# 5_power_supply.net
KiCad netlist of a schematic drawn in Altium Designer
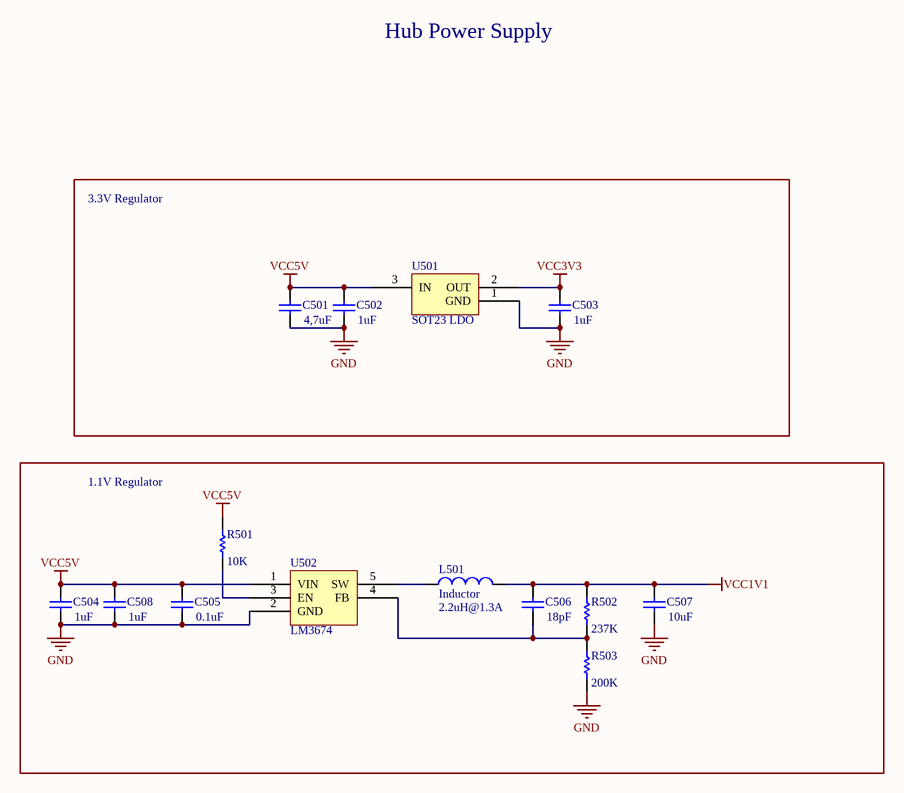
[diagram p0: 5_power_supply.SchDoc]

(export (version "E")
  (design (tool "Eeschema 10.0.6"))
  (components
    (comp (ref "C501")
      (value "4,7uF")
      (footprint "C0603[1608]")
      (description "Capacitor")
      (fields (field (name "LCSC PART #") "C19666") (field (name "MRF.PART") "CL10A475KO8NNNC"))
      (libsource (lib "Miscellaneous Devices") (part "Cap"))
    )
    (comp (ref "C502")
      (value "1uF")
      (footprint "C0603[1608]")
      (description "Capacitor")
      (fields (field (name "MFG") "KEMET") (field (name "LCSC PART #") "C15849"))
      (libsource (lib "Miscellaneous Devices") (part "Cap"))
    )
    (comp (ref "C503")
      (value "1uF")
      (footprint "C0603[1608]")
      (description "Capacitor")
      (fields (field (name "MFG") "KEMET") (field (name "LCSC PART #") "C15849"))
      (libsource (lib "Miscellaneous Devices") (part "Cap"))
    )
    (comp (ref "C504")
      (value "1uF")
      (footprint "C0603[1608]")
      (description "Capacitor")
      (fields (field (name "MFG") "KEMET") (field (name "LCSC PART #") "C15849"))
      (libsource (lib "Miscellaneous Devices") (part "Cap"))
    )
    (comp (ref "C505")
      (value "0.1uF")
      (footprint "C0603[1608]")
      (description "Capacitor")
      (fields (field (name "MFG") "KEMET") (field (name "LCSC PART #") "C14663"))
      (libsource (lib "Miscellaneous Devices") (part "Cap"))
    )
    (comp (ref "C506")
      (value "18pF")
      (footprint "C0603[1608]")
      (description "Capacitor")
      (fields (field (name "MFG") "KEMET") (field (name "LCSC PART #") "C1647"))
      (libsource (lib "Miscellaneous Devices") (part "Cap"))
    )
    (comp (ref "C507")
      (value "10uF")
      (footprint "C1206[3216]")
      (description "Capacitor")
      (fields (field (name "MFG") "KEMET") (field (name "LCSC PART #") "C13585"))
      (libsource (lib "Miscellaneous Devices") (part "Cap"))
    )
    (comp (ref "C508")
      (value "1uF")
      (footprint "C0603[1608]")
      (description "Capacitor")
      (fields (field (name "MFG") "KEMET") (field (name "LCSC PART #") "C15849"))
      (libsource (lib "Miscellaneous Devices") (part "Cap"))
    )
    (comp (ref "L501")
      (value "Inductor")
      (footprint "CDRH2D14")
      (fields
        (field (name "ALTIUM_VALUE") "2.2uH@1.3A")
        (field (name "MFG") "Sumida")
        (field (name "LCSC PART #") "C167267")
        (field (name "MRF.PART") "CDRH2D14NP-2R2NC")
      )
      (libsource (lib "Miscellaneous Devices") (part "Inductor"))
    )
    (comp (ref "R501")
      (value "10K")
      (footprint "R0603[1608]")
      (description "Resistor")
      (fields (field (name "MFG") "Vishay Dale") (field (name "LCSC PART #") "C25804"))
      (libsource (lib "Miscellaneous Devices") (part "Res1"))
    )
    (comp (ref "R502")
      (value "237K")
      (footprint "R0603[1608]")
      (description "Resistor")
      (fields (field (name "MFG") "Vishay Dale") (field (name "LCSC PART #") "C22914"))
      (libsource (lib "Miscellaneous Devices") (part "Res1"))
    )
    (comp (ref "R503")
      (value "200K")
      (footprint "R0603[1608]")
      (description "Resistor")
      (fields (field (name "MFG") "Vishay Dale") (field (name "LCSC PART #") "C25811"))
      (libsource (lib "Miscellaneous Devices") (part "Res1"))
    )
    (comp (ref "U501")
      (value "SOT23 LDO")
      (footprint "SOT-23-3")
      (fields
        (field (name "LCSC PART #") "C5446")
        (field (name "MRF.PART") "XC6206P332MR")
        (field (name "MFG") "Texas Instruments")
      )
      (libsource (lib "Keebs") (part "SOT23 LDO"))
    )
    (comp (ref "U502")
      (value "LM3674")
      (footprint "SOT-23-5")
      (fields
        (field (name "MFG") "Texas Instruments")
        (field (name "LCSC PART #") "C52027")
        (field (name "MRF.PART") "LM3674MF-ADJ/NOPB")
      )
      (libsource (lib "lib") (part "LM3674"))
    )
  )
  (nets
    (net (code "1") (name "GND") (class "Default")
      (node (ref "C501") (pin "1") (pinfunction "1_1") (pintype "passive"))
      (node (ref "C502") (pin "1") (pinfunction "1_1") (pintype "passive"))
      (node (ref "C503") (pin "1") (pinfunction "1_1") (pintype "passive"))
      (node (ref "C504") (pin "1") (pinfunction "1_1") (pintype "passive"))
      (node (ref "C505") (pin "1") (pinfunction "1_1") (pintype "passive"))
      (node (ref "C507") (pin "1") (pinfunction "1_1") (pintype "passive"))
      (node (ref "C508") (pin "1") (pinfunction "1_1") (pintype "passive"))
      (node (ref "R503") (pin "2") (pinfunction "2_2") (pintype "passive"))
      (node (ref "U501") (pin "1") (pinfunction "GND_1") (pintype "passive"))
      (node (ref "U502") (pin "2") (pinfunction "GND_2") (pintype "passive"))
    )
    (net (code "2") (name "Net-(U502-EN)") (class "Default")
      (node (ref "R501") (pin "2") (pinfunction "2_2") (pintype "passive"))
      (node (ref "U502") (pin "3") (pinfunction "EN_3") (pintype "passive"))
    )
    (net (code "3") (name "Net-(U502-FB)") (class "Default")
      (node (ref "C506") (pin "1") (pinfunction "1_1") (pintype "passive"))
      (node (ref "R502") (pin "2") (pinfunction "2_2") (pintype "passive"))
      (node (ref "R503") (pin "1") (pinfunction "1_1") (pintype "passive"))
      (node (ref "U502") (pin "4") (pinfunction "FB_4") (pintype "passive"))
    )
    (net (code "4") (name "Net-(U502-SW)") (class "Default")
      (node (ref "L501") (pin "1") (pinfunction "1_1") (pintype "passive"))
      (node (ref "U502") (pin "5") (pinfunction "SW_5") (pintype "passive"))
    )
    (net (code "5") (name "VCC1V1") (class "Default")
      (node (ref "C506") (pin "2") (pinfunction "2_2") (pintype "passive"))
      (node (ref "C507") (pin "2") (pinfunction "2_2") (pintype "passive"))
      (node (ref "L501") (pin "2") (pinfunction "2_2") (pintype "passive"))
      (node (ref "R502") (pin "1") (pinfunction "1_1") (pintype "passive"))
    )
    (net (code "6") (name "VCC3V3") (class "Default")
      (node (ref "C503") (pin "2") (pinfunction "2_2") (pintype "passive"))
      (node (ref "U501") (pin "2") (pinfunction "OUT_2") (pintype "passive"))
    )
    (net (code "7") (name "VCC5V") (class "Default")
      (node (ref "C501") (pin "2") (pinfunction "2_2") (pintype "passive"))
      (node (ref "C502") (pin "2") (pinfunction "2_2") (pintype "passive"))
      (node (ref "C504") (pin "2") (pinfunction "2_2") (pintype "passive"))
      (node (ref "C505") (pin "2") (pinfunction "2_2") (pintype "passive"))
      (node (ref "C508") (pin "2") (pinfunction "2_2") (pintype "passive"))
      (node (ref "R501") (pin "1") (pinfunction "1_1") (pintype "passive"))
      (node (ref "U501") (pin "3") (pinfunction "IN_3") (pintype "passive"))
      (node (ref "U502") (pin "1") (pinfunction "VIN_1") (pintype "passive"))
    )
  )
)
